# 5VSecondary.net
KiCad netlist of a schematic drawn in Altium Designer
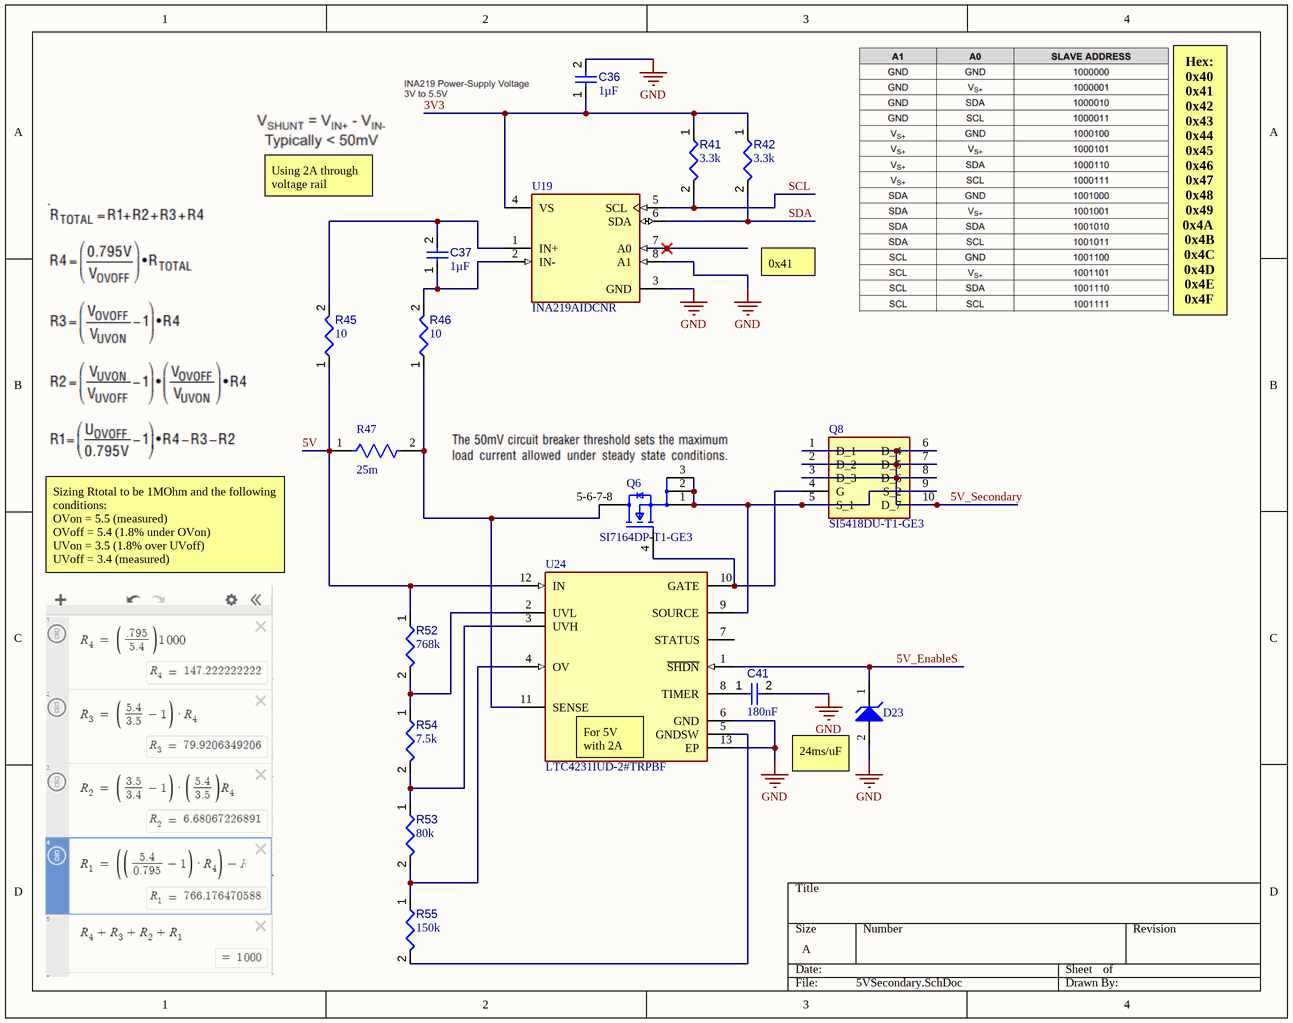
[diagram p0: 5VSecondary.SchDoc]

(export (version "E")
  (design (tool "Eeschema 10.0.6"))
  (components
    (comp (ref "C36")
      (value "1µF")
      (footprint "CAPC1608X90X35ML15T15")
      (description "Chip Capacitor, 1 uF, +/- 10%, 16 V, 0603 (1608 Metric)")
      (fields (field (name "TOLERANCE") "10%") (field (name "Comment") "Capacitor 1uF +/- 10% 16V 0603"))
      (libsource (lib "UGA SSRL Hardware Team") (part "CAP-NP-2"))
    )
    (comp (ref "C37")
      (value "1µF")
      (footprint "CAPC1608X90X40LL10T20")
      (description "Chip Capacitor, 1 uF, +/- 10%, 25 V, 0603 (1608 Metric)")
      (fields (field (name "TOLERANCE") "10%") (field (name "Comment") "Capacitor 1 uF +/- 10% 25 V 0603"))
      (libsource (lib "UGA SSRL Hardware Team") (part "CAP-NP-2"))
    )
    (comp (ref "C41")
      (value "180nF")
      (footprint "FP-C0805C-DN-IPC_A")
      (fields (field (name "Comment") "C0805C184K5RACTU"))
      (libsource (lib "UGA SSRL Hardware Team") (part "CAP-NP-2"))
    )
    (comp (ref "D23")
      (value "MM3Z3V6T1G")
      (footprint "ONSC-SOD-323-2-477-02_V")
      (description "Zener Voltage Regulator, 300 mW, 2-Pin SOD-323, Pb-Free, Tape and Reel")
      (fields (field (name "MANUFACTURER") "On Semiconductor"))
      (libsource (lib "Altium Content Vault") (part "ONSC-K1A2-2"))
    )
    (comp (ref "Q6")
      (value "SI7164DP-T1-GE3")
      (footprint "Vishay_S17-0173-SINGLE_MFG")
      (libsource (lib "UGA SSRL Hardware Team") (part "SI7164DP-T1-GE3"))
    )
    (comp (ref "Q8")
      (value "SI5418DU-T1-GE3")
      (footprint "SI5418DU-T1-GE3-Footprint-1")
      (libsource (lib "UGA SSRL Hardware Team") (part "SI5418DU-T1-GE3-Symbol-1"))
    )
    (comp (ref "R41")
      (value "3.3k")
      (footprint "FP-CRCW1210-e3-IPC_C")
      (fields
        (field (name "TOLERANCE") "5%")
        (field (name "POWER") "500mW")
        (field (name "Comment") "CRCW12103K30JNEA")
      )
      (libsource (lib "UGA SSRL Hardware Team") (part "RES-2"))
    )
    (comp (ref "R42")
      (value "3.3k")
      (footprint "FP-CRCW1210-e3-IPC_C")
      (fields
        (field (name "TOLERANCE") "5%")
        (field (name "POWER") "500mW")
        (field (name "Comment") "CRCW12103K30JNEA")
      )
      (libsource (lib "UGA SSRL Hardware Team") (part "RES-2"))
    )
    (comp (ref "R45")
      (value "10")
      (footprint "RESC0402(1005)_L")
      (description "Chip Resistor, 10 Ohms, +/-1 %, 63 mW, -55 to 155 degC, 0402")
      (fields (field (name "TOLERANCE") "1%") (field (name "POWER") "63mW"))
      (libsource (lib "UGA SSRL Hardware Team") (part "RES-2"))
    )
    (comp (ref "R46")
      (value "10")
      (footprint "RESC0402(1005)_L")
      (description "Chip Resistor, 10 Ohms, +/-1 %, 63 mW, -55 to 155 degC, 0402")
      (fields (field (name "TOLERANCE") "1%") (field (name "POWER") "63mW"))
      (libsource (lib "UGA SSRL Hardware Team") (part "RES-2"))
    )
    (comp (ref "R47")
      (value "CSR1206FK25L0")
      (footprint "FP-CSR1206-IPC_C")
      (description "General Purpose Thick Film Chip Resistor, 1206, 25mΩ, 1%, 0.5W")
      (fields (field (name "RESISTANCE") "25m") (field (name "TOLERANCE") "1%"))
      (libsource (lib "Altium Content Vault") (part "1029c3af85768c4190bb7ad29bc67b5"))
    )
    (comp (ref "R52")
      (value "768k")
      (footprint "RESC0402(1005)_L")
      (description "768K 0.063W 1% 0402 (1005 Metric)  SMD")
      (fields (field (name "TOLERANCE") "1%") (field (name "POWER") "63mW"))
      (libsource (lib "UGA SSRL Hardware Team") (part "768KR2F"))
    )
    (comp (ref "R53")
      (value "80k")
      (footprint "FP-PTN0603-IPC_B")
      (description "Fixed Resistor, Thin Film, 0.15W, 80000ohm, 75V, 0.1% +/-Tol, 25ppm/Cel, Surface Mount, 0603")
      (fields (field (name "POWER") "150mW") (field (name "TOLERANCE") "0.1%"))
      (libsource (lib "UGA SSRL Hardware Team") (part "RES-2"))
    )
    (comp (ref "R54")
      (value "7.5k")
      (footprint "FP-CRCW1206-e3-IPC_A")
      (fields
        (field (name "TOLERANCE") "1%")
        (field (name "POWER") "250mW")
        (field (name "Comment") "CRCW12067K50FKEA")
      )
      (libsource (lib "UGA SSRL Hardware Team") (part "RES-2"))
    )
    (comp (ref "R55")
      (value "150k")
      (footprint "FP-RT1206-IPC_C")
      (description "Fixed Resistor, Thin Film, 0.25W, 150000ohm, 200V, 1% +/-Tol, 50ppm/Cel, Surface Mount, 1206")
      (fields (field (name "TOLERANCE") "1%") (field (name "POWER") "250mW"))
      (libsource (lib "UGA SSRL Hardware Team") (part "RES-2"))
    )
    (comp (ref "U19")
      (value "INA219AIDCNR")
      (footprint "FP-DCN0008A-IPC_A")
      (description "Power Supply Support Circuit, Fixed, 2 Channel, 2V, PDSO8")
      (libsource (lib "UGA SSRL Hardware Team") (part "e16934b8ef90d0e345b266f0ae9cd81"))
    )
    (comp (ref "U24")
      (value "LTC4231IUD-2#TRPBF")
      (footprint "FP-UD-12-05-08-1855-IPC_A")
      (description "Switching Controller, CMOS, PQCC12")
      (libsource (lib "UGA SSRL Hardware Team") (part "94c330ae140e2337d879337fe7aaeec"))
    )
  )
  (nets
    (net (code "1") (name "/3V3") (class "Default")
      (node (ref "C36") (pin "1") (pinfunction "1_1") (pintype "passive"))
      (node (ref "R41") (pin "1") (pinfunction "1_1") (pintype "passive"))
      (node (ref "R42") (pin "1") (pinfunction "1_1") (pintype "passive"))
      (node (ref "U19") (pin "4") (pinfunction "VS_4") (pintype "power_in"))
    )
    (net (code "2") (name "/5V") (class "Default")
      (node (ref "R45") (pin "1") (pinfunction "1_1") (pintype "passive"))
      (node (ref "R47") (pin "1") (pinfunction "1_1") (pintype "passive"))
      (node (ref "R52") (pin "1") (pinfunction "1_1") (pintype "passive"))
      (node (ref "U24") (pin "12") (pinfunction "IN_12") (pintype "input"))
    )
    (net (code "3") (name "/5V_EnableS") (class "Default")
      (node (ref "D23") (pin "1") (pinfunction "K_1") (pintype "passive"))
      (node (ref "U24") (pin "1") (pinfunction "~{SHDN}_1") (pintype "input"))
    )
    (net (code "4") (name "/5V_Secondary") (class "Default")
      (node (ref "Q8") (pin "1") (pinfunction "D_1_1") (pintype "passive"))
      (node (ref "Q8") (pin "10") (pinfunction "D_7_10") (pintype "passive"))
      (node (ref "Q8") (pin "2") (pinfunction "D_2_2") (pintype "passive"))
      (node (ref "Q8") (pin "3") (pinfunction "D_3_3") (pintype "passive"))
      (node (ref "Q8") (pin "6") (pinfunction "D_4_6") (pintype "passive"))
      (node (ref "Q8") (pin "7") (pinfunction "D_5_7") (pintype "passive"))
      (node (ref "Q8") (pin "8") (pinfunction "D_6_8") (pintype "passive"))
    )
    (net (code "5") (name "/SCL") (class "Default")
      (node (ref "R41") (pin "2") (pinfunction "2_2") (pintype "passive"))
      (node (ref "U19") (pin "5") (pinfunction "SCL_5") (pintype "input"))
    )
    (net (code "6") (name "/SDA") (class "Default")
      (node (ref "R42") (pin "2") (pinfunction "2_2") (pintype "passive"))
      (node (ref "U19") (pin "6") (pinfunction "SDA_6") (pintype "bidirectional"))
    )
    (net (code "7") (name "GND") (class "Default")
      (node (ref "C36") (pin "2") (pinfunction "2_2") (pintype "passive"))
      (node (ref "C41") (pin "2") (pinfunction "2_2") (pintype "passive"))
      (node (ref "D23") (pin "2") (pinfunction "A_2") (pintype "passive"))
      (node (ref "U19") (pin "3") (pinfunction "GND_3") (pintype "power_in"))
      (node (ref "U19") (pin "8") (pinfunction "A1_8") (pintype "input"))
      (node (ref "U24") (pin "13") (pinfunction "EP_13") (pintype "power_in"))
      (node (ref "U24") (pin "6") (pinfunction "GND_6") (pintype "power_in"))
    )
    (net (code "8") (name "Net-(Q6-D)") (class "Default")
      (node (ref "Q6") (pin "5-6-7-8") (pinfunction "D_5-6-7-8") (pintype "passive"))
      (node (ref "R46") (pin "1") (pinfunction "1_1") (pintype "passive"))
      (node (ref "R47") (pin "2") (pinfunction "2_2") (pintype "passive"))
      (node (ref "U24") (pin "11") (pinfunction "SENSE_11") (pintype "passive"))
    )
    (net (code "9") (name "Net-(Q6-G)") (class "Default")
      (node (ref "Q6") (pin "4") (pinfunction "G_4") (pintype "passive"))
      (node (ref "Q8") (pin "4") (pinfunction "G_4") (pintype "passive"))
      (node (ref "U24") (pin "10") (pinfunction "GATE_10") (pintype "passive"))
    )
    (net (code "10") (name "Net-(Q8-S_1)") (class "Default")
      (node (ref "Q6") (pin "1") (pinfunction "S_1") (pintype "passive"))
      (node (ref "Q6") (pin "2") (pinfunction "S_2") (pintype "passive"))
      (node (ref "Q6") (pin "3") (pinfunction "S_3") (pintype "passive"))
      (node (ref "Q8") (pin "5") (pinfunction "S_1_5") (pintype "passive"))
      (node (ref "Q8") (pin "9") (pinfunction "S_2_9") (pintype "passive"))
      (node (ref "U24") (pin "9") (pinfunction "SOURCE_9") (pintype "passive"))
    )
    (net (code "11") (name "Net-(U19-IN+)") (class "Default")
      (node (ref "C37") (pin "2") (pinfunction "2_2") (pintype "passive"))
      (node (ref "R45") (pin "2") (pinfunction "2_2") (pintype "passive"))
      (node (ref "U19") (pin "1") (pinfunction "IN+_1") (pintype "passive"))
    )
    (net (code "12") (name "Net-(U19-IN-)") (class "Default")
      (node (ref "C37") (pin "1") (pinfunction "1_1") (pintype "passive"))
      (node (ref "R46") (pin "2") (pinfunction "2_2") (pintype "passive"))
      (node (ref "U19") (pin "2") (pinfunction "IN-_2") (pintype "input"))
    )
    (net (code "13") (name "Net-(U24-GNDSW)") (class "Default")
      (node (ref "R55") (pin "2") (pinfunction "2_2") (pintype "passive"))
      (node (ref "U24") (pin "5") (pinfunction "GNDSW_5") (pintype "power_in"))
    )
    (net (code "14") (name "Net-(U24-OV)") (class "Default")
      (node (ref "R53") (pin "2") (pinfunction "2_2") (pintype "passive"))
      (node (ref "R55") (pin "1") (pinfunction "1_1") (pintype "passive"))
      (node (ref "U24") (pin "4") (pinfunction "OV_4") (pintype "input"))
    )
    (net (code "15") (name "Net-(U24-TIMER)") (class "Default")
      (node (ref "C41") (pin "1") (pinfunction "1_1") (pintype "passive"))
      (node (ref "U24") (pin "8") (pinfunction "TIMER_8") (pintype "passive"))
    )
    (net (code "16") (name "Net-(U24-UVH)") (class "Default")
      (node (ref "R53") (pin "1") (pinfunction "1_1") (pintype "passive"))
      (node (ref "R54") (pin "2") (pinfunction "2_2") (pintype "passive"))
      (node (ref "U24") (pin "3") (pinfunction "UVH_3") (pintype "passive"))
    )
    (net (code "17") (name "Net-(U24-UVL)") (class "Default")
      (node (ref "R52") (pin "2") (pinfunction "2_2") (pintype "passive"))
      (node (ref "R54") (pin "1") (pinfunction "1_1") (pintype "passive"))
      (node (ref "U24") (pin "2") (pinfunction "UVL_2") (pintype "passive"))
    )
    (net (code "18") (name "unconnected-(U19-A0-Pad7)") (class "Default")
      (node (ref "U19") (pin "7") (pinfunction "A0_7") (pintype "input+no_connect"))
    )
    (net (code "19") (name "unconnected-(U24-STATUS-Pad7)") (class "Default")
      (node (ref "U24") (pin "7") (pinfunction "STATUS_7") (pintype "passive"))
    )
  )
)
